# MJ808_clone_-_all_driver_-_POC.net
KiCad netlist of a schematic drawn in EAGLE
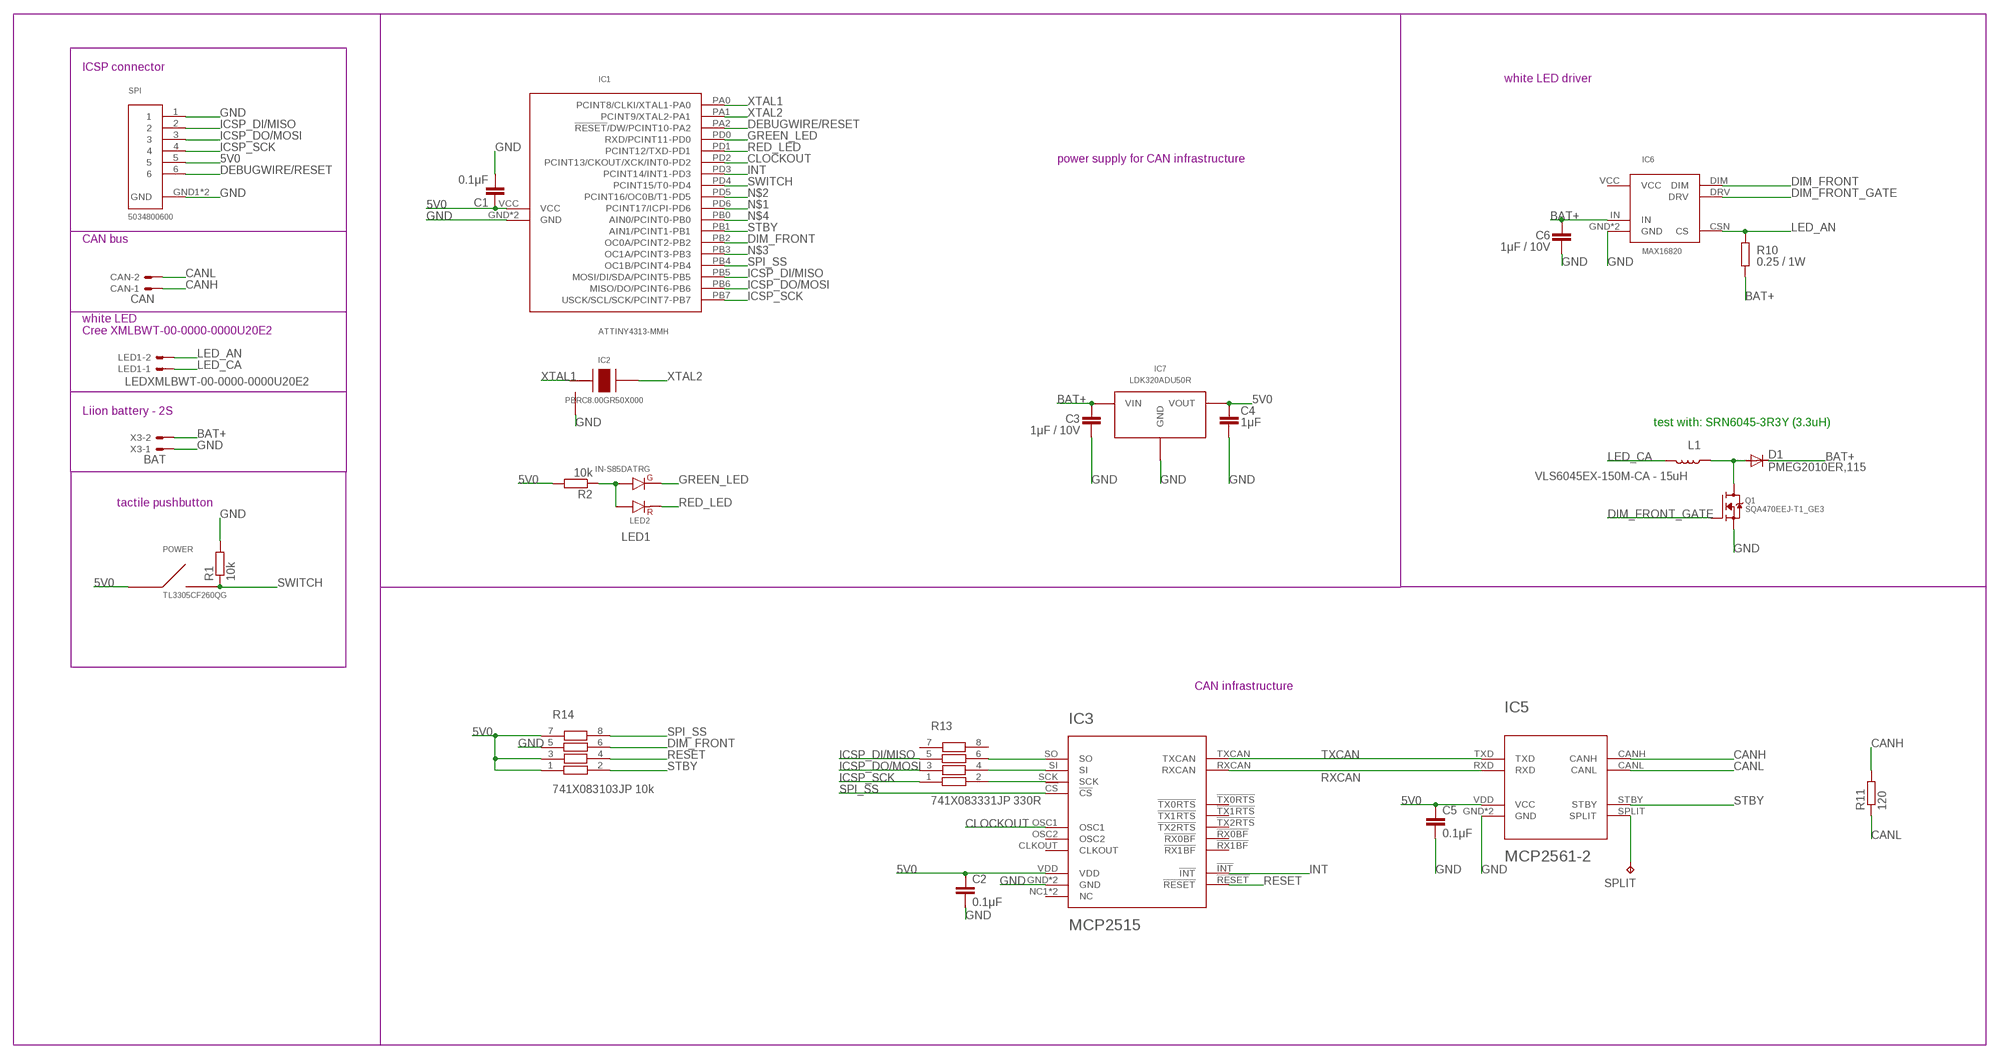
[diagram p0: schematic, sheet 1]

(export (version "E")
  (design (tool "Eeschema 10.0.6"))
  (components
    (comp (ref "C1")
      (value "0.1μF")
      (footprint "eagle-import:C0402")
      (libsource (lib "eagle-import") (part "C-EUC0402"))
    )
    (comp (ref "C2")
      (value "0.1μF")
      (footprint "eagle-import:C0402")
      (libsource (lib "eagle-import") (part "C-EUC0402"))
    )
    (comp (ref "C3")
      (value "1μF / 10V")
      (footprint "eagle-import:C0402")
      (libsource (lib "eagle-import") (part "C-EUC0402"))
    )
    (comp (ref "C4")
      (value "1μF")
      (footprint "eagle-import:C0402")
      (libsource (lib "eagle-import") (part "C-EUC0402"))
    )
    (comp (ref "C5")
      (value "0.1μF")
      (footprint "eagle-import:C0402")
      (libsource (lib "eagle-import") (part "C-EUC0402"))
    )
    (comp (ref "C6")
      (value "1μF / 10V")
      (footprint "eagle-import:C0402")
      (libsource (lib "eagle-import") (part "C-EUC0402"))
    )
    (comp (ref "CAN")
      (value "CAN")
      (footprint "eagle-import:22-23-2021")
      (fields (field (name "MF") "MOLEX") (field (name "MPN") "22-23-2021"))
      (libsource (lib "eagle-import") (part "22-23-2021"))
    )
    (comp (ref "D1")
      (value "PMEG2010ER,115")
      (footprint "eagle-import:SOD123")
      (libsource (lib "eagle-import") (part "DIODE-SOD123"))
    )
    (comp (ref "IC1")
      (value "ATTINY4313-MMH")
      (footprint "eagle-import:VQFN-20")
      (fields (field (name "SPICEPREFIX") "X"))
      (libsource (lib "eagle-import") (part "ATTINY4313VQFN-20"))
    )
    (comp (ref "IC2")
      (value "PBRC8.00GR50X000")
      (footprint "eagle-import:SMT")
      (libsource (lib "eagle-import") (part "PRQV"))
    )
    (comp (ref "IC3")
      (value "MCP2515")
      (footprint "eagle-import:QFN20")
      (libsource (lib "eagle-import") (part "MCP2515-I-ML"))
    )
    (comp (ref "IC5")
      (value "MCP2561-2")
      (footprint "eagle-import:DFN10")
      (libsource (lib "eagle-import") (part "MCP2561-2"))
    )
    (comp (ref "IC6")
      (value "MAX16820")
      (footprint "eagle-import:TDFN-6-EP")
      (libsource (lib "eagle-import") (part "MAX16820"))
    )
    (comp (ref "IC7")
      (value "LDK320ADU50R")
      (footprint "eagle-import:SOT-89")
      (libsource (lib "eagle-import") (part "LDO"))
    )
    (comp (ref "L1")
      (value "VLS6045EX-150M-CA - 15uH")
      (footprint "eagle-import:SRN6045")
      (libsource (lib "eagle-import") (part "INDUCTOR-SRN6045-33UH"))
    )
    (comp (ref "LED1")
      (value "LEDXMLBWT-00-0000-0000U20E2")
      (footprint "eagle-import:22-23-2021")
      (fields (field (name "MF") "MOLEX") (field (name "MPN") "22-23-2021"))
      (libsource (lib "eagle-import") (part "22-23-2021"))
    )
    (comp (ref "LED2")
      (value "IN-S85DATRG")
      (footprint "eagle-import:SMD")
      (libsource (lib "eagle-import") (part "APHBM2012LSURKZGKC"))
    )
    (comp (ref "POWER")
      (value "TL3305CF260QG")
      (footprint "eagle-import:SMD")
      (libsource (lib "eagle-import") (part "TL3305-844809"))
    )
    (comp (ref "Q1")
      (value "SQA470EEJ-T1_GE3")
      (footprint "eagle-import:SC-70-6")
      (libsource (lib "eagle-import") (part "SIA456DJ"))
    )
    (comp (ref "R1")
      (value "10k")
      (footprint "eagle-import:R0402")
      (libsource (lib "eagle-import") (part "R-EU_R0402"))
    )
    (comp (ref "R2")
      (value "10k")
      (footprint "eagle-import:R0402")
      (libsource (lib "eagle-import") (part "R-EU_R0402"))
    )
    (comp (ref "R10")
      (value "0.25 / 1W")
      (footprint "eagle-import:R1210")
      (libsource (lib "eagle-import") (part "R-EU_R1210"))
    )
    (comp (ref "R11")
      (value "120")
      (footprint "eagle-import:R0805")
      (libsource (lib "eagle-import") (part "R-EU_R0805"))
    )
    (comp (ref "R13")
      (value "741X083331JP 330R")
      (footprint "eagle-import:0402")
      (libsource (lib "eagle-import") (part "741X083331JP"))
    )
    (comp (ref "R14")
      (value "741X083103JP 10k")
      (footprint "eagle-import:0402")
      (libsource (lib "eagle-import") (part "741X083331JP"))
    )
    (comp (ref "SPI")
      (value "5034800600")
      (footprint "eagle-import:SMT")
      (libsource (lib "eagle-import") (part "5034800600"))
    )
    (comp (ref "SPLIT")
      (value "TPB2,54")
      (footprint "eagle-import:B2,54")
      (libsource (lib "eagle-import") (part "TPB2,54"))
    )
    (comp (ref "X3")
      (value "BAT")
      (footprint "eagle-import:22-23-2021")
      (fields (field (name "MF") "MOLEX") (field (name "MPN") "22-23-2021"))
      (libsource (lib "eagle-import") (part "22-23-2021"))
    )
  )
  (nets
    (net (code "1") (name "/5V0") (class "Default")
      (node (ref "C1") (pin "1") (pinfunction "1_1") (pintype "passive"))
      (node (ref "C2") (pin "1") (pinfunction "1_1") (pintype "passive"))
      (node (ref "C4") (pin "2") (pinfunction "2_2") (pintype "passive"))
      (node (ref "C5") (pin "1") (pinfunction "1_1") (pintype "passive"))
      (node (ref "IC1") (pin "VCC") (pinfunction "VCC_VCC") (pintype "bidirectional"))
      (node (ref "IC3") (pin "VDD") (pinfunction "VDD_VDD") (pintype "power_in"))
      (node (ref "IC5") (pin "VDD") (pinfunction "VCC_VDD") (pintype "power_in"))
      (node (ref "IC7") (pin "VOUT") (pinfunction "VOUT_VOUT") (pintype "bidirectional"))
      (node (ref "POWER") (pin "1") (pinfunction "P$1_1") (pintype "bidirectional"))
      (node (ref "POWER") (pin "2") (pinfunction "P$1_2") (pintype "bidirectional"))
      (node (ref "R14") (pin "1") (pinfunction "1_1") (pintype "bidirectional"))
      (node (ref "R14") (pin "3") (pinfunction "3_3") (pintype "bidirectional"))
      (node (ref "R14") (pin "7") (pinfunction "7_7") (pintype "bidirectional"))
      (node (ref "R2") (pin "2") (pinfunction "2_2") (pintype "passive"))
      (node (ref "SPI") (pin "5") (pinfunction "5_5") (pintype "bidirectional"))
    )
    (net (code "2") (name "/BAT+") (class "Default")
      (node (ref "C3") (pin "1") (pinfunction "1_1") (pintype "passive"))
      (node (ref "C6") (pin "1") (pinfunction "1_1") (pintype "passive"))
      (node (ref "D1") (pin "C") (pinfunction "C_C") (pintype "passive"))
      (node (ref "IC6") (pin "IN") (pinfunction "IN_IN") (pintype "power_in"))
      (node (ref "IC7") (pin "VIN") (pinfunction "VIN_VIN") (pintype "bidirectional"))
      (node (ref "R10") (pin "2") (pinfunction "2_2") (pintype "passive"))
      (node (ref "X3") (pin "2") (pinfunction "S_2") (pintype "passive"))
    )
    (net (code "3") (name "/CANH") (class "Default")
      (node (ref "CAN") (pin "1") (pinfunction "S_1") (pintype "passive"))
      (node (ref "IC5") (pin "CANH") (pinfunction "CANH_CANH") (pintype "bidirectional"))
      (node (ref "R11") (pin "2") (pinfunction "2_2") (pintype "passive"))
    )
    (net (code "4") (name "/CANL") (class "Default")
      (node (ref "CAN") (pin "2") (pinfunction "S_2") (pintype "passive"))
      (node (ref "IC5") (pin "CANL") (pinfunction "CANL_CANL") (pintype "bidirectional"))
      (node (ref "R11") (pin "1") (pinfunction "1_1") (pintype "passive"))
    )
    (net (code "5") (name "/CLOCKOUT") (class "Default")
      (node (ref "IC1") (pin "PD2") (pinfunction "PCINT13/CKOUT/XCK/INT0-PD2_PD2") (pintype "bidirectional"))
      (node (ref "IC3") (pin "OSC1") (pinfunction "OSC1_OSC1") (pintype "bidirectional"))
    )
    (net (code "6") (name "/DEBUGWIRE{slash}RESET") (class "Default")
      (node (ref "IC1") (pin "PA2") (pinfunction "~{RESET}/DW/PCINT10-PA2_PA2") (pintype "bidirectional"))
      (node (ref "SPI") (pin "6") (pinfunction "6_6") (pintype "bidirectional"))
    )
    (net (code "7") (name "/DIM_FRONT") (class "Default")
      (node (ref "IC1") (pin "PB2") (pinfunction "OC0A/PCINT2-PB2_PB2") (pintype "bidirectional"))
      (node (ref "IC6") (pin "DIM") (pinfunction "DIM_DIM") (pintype "bidirectional"))
      (node (ref "R14") (pin "6") (pinfunction "6_6") (pintype "bidirectional"))
    )
    (net (code "8") (name "/DIM_FRONT_GATE") (class "Default")
      (node (ref "IC6") (pin "DRV") (pinfunction "DRV_DRV") (pintype "bidirectional"))
      (node (ref "Q1") (pin "G") (pinfunction "G_G") (pintype "passive"))
    )
    (net (code "9") (name "/GND") (class "Default")
      (node (ref "C1") (pin "2") (pinfunction "2_2") (pintype "passive"))
      (node (ref "C2") (pin "2") (pinfunction "2_2") (pintype "passive"))
      (node (ref "C3") (pin "2") (pinfunction "2_2") (pintype "passive"))
      (node (ref "C4") (pin "1") (pinfunction "1_1") (pintype "passive"))
      (node (ref "C5") (pin "2") (pinfunction "2_2") (pintype "passive"))
      (node (ref "C6") (pin "2") (pinfunction "2_2") (pintype "passive"))
      (node (ref "IC1") (pin "GND") (pinfunction "GND_GND") (pintype "bidirectional"))
      (node (ref "IC1") (pin "GND1") (pinfunction "GND_GND1") (pintype "bidirectional"))
      (node (ref "IC2") (pin "GND") (pinfunction "GND_GND") (pintype "bidirectional"))
      (node (ref "IC3") (pin "GND") (pinfunction "GND_GND") (pintype "power_in"))
      (node (ref "IC3") (pin "GND6") (pinfunction "GND_GND6") (pintype "power_in"))
      (node (ref "IC5") (pin "GND") (pinfunction "GND_GND") (pintype "power_in"))
      (node (ref "IC5") (pin "VSS") (pinfunction "GND_VSS") (pintype "power_in"))
      (node (ref "IC6") (pin "GND") (pinfunction "GND_GND") (pintype "power_in"))
      (node (ref "IC6") (pin "GND1") (pinfunction "GND_GND1") (pintype "power_in"))
      (node (ref "IC7") (pin "GND") (pinfunction "GND_GND") (pintype "bidirectional"))
      (node (ref "Q1") (pin "S") (pinfunction "S_S") (pintype "passive"))
      (node (ref "R1") (pin "2") (pinfunction "2_2") (pintype "passive"))
      (node (ref "R14") (pin "5") (pinfunction "5_5") (pintype "bidirectional"))
      (node (ref "SPI") (pin "1") (pinfunction "1_1") (pintype "bidirectional"))
      (node (ref "SPI") (pin "GND1") (pinfunction "GND_GND1") (pintype "bidirectional"))
      (node (ref "SPI") (pin "GND2") (pinfunction "GND_GND2") (pintype "bidirectional"))
      (node (ref "X3") (pin "1") (pinfunction "S_1") (pintype "passive"))
    )
    (net (code "10") (name "/GREEN_LED") (class "Default")
      (node (ref "IC1") (pin "PD0") (pinfunction "RXD/PCINT11-PD0_PD0") (pintype "bidirectional"))
      (node (ref "LED2") (pin "3") (pinfunction "3_3") (pintype "bidirectional"))
    )
    (net (code "11") (name "/ICSP_DI{slash}MISO") (class "Default")
      (node (ref "IC1") (pin "PB5") (pinfunction "MOSI/DI/SDA/PCINT5-PB5_PB5") (pintype "bidirectional"))
      (node (ref "R13") (pin "5") (pinfunction "5_5") (pintype "bidirectional"))
      (node (ref "SPI") (pin "2") (pinfunction "2_2") (pintype "bidirectional"))
    )
    (net (code "12") (name "/ICSP_DO{slash}MOSI") (class "Default")
      (node (ref "IC1") (pin "PB6") (pinfunction "MISO/DO/PCINT6-PB6_PB6") (pintype "bidirectional"))
      (node (ref "R13") (pin "3") (pinfunction "3_3") (pintype "bidirectional"))
      (node (ref "SPI") (pin "3") (pinfunction "3_3") (pintype "bidirectional"))
    )
    (net (code "13") (name "/ICSP_SCK") (class "Default")
      (node (ref "IC1") (pin "PB7") (pinfunction "USCK/SCL/SCK/PCINT7-PB7_PB7") (pintype "bidirectional"))
      (node (ref "R13") (pin "1") (pinfunction "1_1") (pintype "bidirectional"))
      (node (ref "SPI") (pin "4") (pinfunction "4_4") (pintype "bidirectional"))
    )
    (net (code "14") (name "/INT") (class "Default")
      (node (ref "IC1") (pin "PD3") (pinfunction "PCINT14/INT1-PD3_PD3") (pintype "bidirectional"))
      (node (ref "IC3") (pin "!INT!") (pinfunction "~{INT}_!INT!") (pintype "bidirectional"))
    )
    (net (code "15") (name "/LED1") (class "Default")
      (node (ref "LED2") (pin "1") (pinfunction "1_1") (pintype "bidirectional"))
      (node (ref "LED2") (pin "4") (pinfunction "4_4") (pintype "bidirectional"))
      (node (ref "R2") (pin "1") (pinfunction "1_1") (pintype "passive"))
    )
    (net (code "16") (name "/LED_AN") (class "Default")
      (node (ref "IC6") (pin "CSN") (pinfunction "CS_CSN") (pintype "bidirectional"))
      (node (ref "LED1") (pin "2") (pinfunction "S_2") (pintype "passive"))
      (node (ref "R10") (pin "1") (pinfunction "1_1") (pintype "passive"))
    )
    (net (code "17") (name "/LED_CA") (class "Default")
      (node (ref "L1") (pin "2") (pinfunction "2_2") (pintype "passive"))
      (node (ref "LED1") (pin "1") (pinfunction "S_1") (pintype "passive"))
    )
    (net (code "18") (name "/N$1") (class "Default")
      (node (ref "IC1") (pin "PD6") (pinfunction "PCINT17/ICPI-PD6_PD6") (pintype "bidirectional"))
    )
    (net (code "19") (name "/N$2") (class "Default")
      (node (ref "IC1") (pin "PD5") (pinfunction "PCINT16/OC0B/T1-PD5_PD5") (pintype "bidirectional"))
    )
    (net (code "20") (name "/N$3") (class "Default")
      (node (ref "IC1") (pin "PB3") (pinfunction "OC1A/PCINT3-PB3_PB3") (pintype "bidirectional"))
    )
    (net (code "21") (name "/N$4") (class "Default")
      (node (ref "IC1") (pin "PB0") (pinfunction "AIN0/PCINT0-PB0_PB0") (pintype "bidirectional"))
    )
    (net (code "22") (name "/RED_LED") (class "Default")
      (node (ref "IC1") (pin "PD1") (pinfunction "PCINT12/TXD-PD1_PD1") (pintype "bidirectional"))
      (node (ref "LED2") (pin "2") (pinfunction "2_2") (pintype "bidirectional"))
    )
    (net (code "23") (name "/RESET") (class "Default")
      (node (ref "IC3") (pin "!RESET!") (pinfunction "~{RESET}_!RESET!") (pintype "bidirectional"))
      (node (ref "R14") (pin "4") (pinfunction "4_4") (pintype "bidirectional"))
    )
    (net (code "24") (name "/RXCAN") (class "Default")
      (node (ref "IC3") (pin "RXCAN") (pinfunction "RXCAN_RXCAN") (pintype "input"))
      (node (ref "IC5") (pin "RXD") (pinfunction "RXD_RXD") (pintype "output"))
    )
    (net (code "25") (name "/SPI_SS") (class "Default")
      (node (ref "IC1") (pin "PB4") (pinfunction "OC1B/PCINT4-PB4_PB4") (pintype "bidirectional"))
      (node (ref "IC3") (pin "!CS!") (pinfunction "~{CS}_!CS!") (pintype "bidirectional"))
      (node (ref "R14") (pin "8") (pinfunction "8_8") (pintype "bidirectional"))
    )
    (net (code "26") (name "/STBY") (class "Default")
      (node (ref "IC1") (pin "PB1") (pinfunction "AIN1/PCINT1-PB1_PB1") (pintype "bidirectional"))
      (node (ref "IC5") (pin "STBY") (pinfunction "STBY_STBY") (pintype "bidirectional"))
      (node (ref "R14") (pin "2") (pinfunction "2_2") (pintype "bidirectional"))
    )
    (net (code "27") (name "/SWITCH") (class "Default")
      (node (ref "IC1") (pin "PD4") (pinfunction "PCINT15/T0-PD4_PD4") (pintype "bidirectional"))
      (node (ref "POWER") (pin "3") (pinfunction "P$2_3") (pintype "bidirectional"))
      (node (ref "POWER") (pin "4") (pinfunction "P$2_4") (pintype "bidirectional"))
      (node (ref "R1") (pin "1") (pinfunction "1_1") (pintype "passive"))
    )
    (net (code "28") (name "/TXCAN") (class "Default")
      (node (ref "IC3") (pin "TXCAN") (pinfunction "TXCAN_TXCAN") (pintype "output"))
      (node (ref "IC5") (pin "TXD") (pinfunction "TXD_TXD") (pintype "input"))
    )
    (net (code "29") (name "/VCC") (class "Default")
      (node (ref "IC6") (pin "VCC") (pinfunction "VCC_VCC") (pintype "power_in"))
    )
    (net (code "30") (name "/XTAL1") (class "Default")
      (node (ref "IC1") (pin "PA0") (pinfunction "PCINT8/CLKI/XTAL1-PA0_PA0") (pintype "bidirectional"))
      (node (ref "IC2") (pin "XTAL1") (pinfunction "XTAL1_XTAL1") (pintype "bidirectional"))
    )
    (net (code "31") (name "/XTAL2") (class "Default")
      (node (ref "IC1") (pin "PA1") (pinfunction "PCINT9/XTAL2-PA1_PA1") (pintype "bidirectional"))
      (node (ref "IC2") (pin "XTAL2") (pinfunction "XTAL2_XTAL2") (pintype "bidirectional"))
    )
    (net (code "32") (name "Net-(D1-PadA)") (class "Default")
      (node (ref "D1") (pin "A") (pinfunction "A_A") (pintype "passive"))
      (node (ref "L1") (pin "1") (pinfunction "1_1") (pintype "passive"))
      (node (ref "Q1") (pin "D") (pinfunction "D_D") (pintype "passive"))
    )
    (net (code "33") (name "Net-(IC3-PadSCK)") (class "Default")
      (node (ref "IC3") (pin "SCK") (pinfunction "SCK_SCK") (pintype "bidirectional"))
      (node (ref "R13") (pin "2") (pinfunction "2_2") (pintype "bidirectional"))
    )
    (net (code "34") (name "Net-(IC3-PadSI)") (class "Default")
      (node (ref "IC3") (pin "SI") (pinfunction "SI_SI") (pintype "input"))
      (node (ref "R13") (pin "4") (pinfunction "4_4") (pintype "bidirectional"))
    )
    (net (code "35") (name "Net-(IC3-PadSO)") (class "Default")
      (node (ref "IC3") (pin "SO") (pinfunction "SO_SO") (pintype "output"))
      (node (ref "R13") (pin "6") (pinfunction "6_6") (pintype "bidirectional"))
    )
    (net (code "36") (name "Net-(IC5-PadSPLIT)") (class "Default")
      (node (ref "IC5") (pin "SPLIT") (pinfunction "SPLIT_SPLIT") (pintype "bidirectional"))
      (node (ref "SPLIT") (pin "TP") (pinfunction "TP_TP") (pintype "input"))
    )
    (net (code "37") (name "unconnected-(IC3-NC-PadNC1)") (class "Default")
      (node (ref "IC3") (pin "NC1") (pinfunction "NC_NC1") (pintype "no_connect"))
    )
    (net (code "38") (name "unconnected-(IC3-NC-PadNC2)") (class "Default")
      (node (ref "IC3") (pin "NC2") (pinfunction "NC_NC2") (pintype "no_connect"))
    )
    (net (code "39") (name "unconnected-(IC3-PadCLKOUT)") (class "Default")
      (node (ref "IC3") (pin "CLKOUT") (pinfunction "CLKOUT_CLKOUT") (pintype "bidirectional"))
    )
    (net (code "40") (name "unconnected-(IC3-PadOSC2)") (class "Default")
      (node (ref "IC3") (pin "OSC2") (pinfunction "OSC2_OSC2") (pintype "bidirectional"))
    )
    (net (code "41") (name "unconnected-(IC3-~{RX0BF}-Pad!RX0BF!)") (class "Default")
      (node (ref "IC3") (pin "!RX0BF!") (pinfunction "~{RX0BF}_!RX0BF!") (pintype "bidirectional"))
    )
    (net (code "42") (name "unconnected-(IC3-~{RX1BF}-Pad!RX1BF!)") (class "Default")
      (node (ref "IC3") (pin "!RX1BF!") (pinfunction "~{RX1BF}_!RX1BF!") (pintype "bidirectional"))
    )
    (net (code "43") (name "unconnected-(IC3-~{TX0RTS}-Pad!TX0RTS!)") (class "Default")
      (node (ref "IC3") (pin "!TX0RTS!") (pinfunction "~{TX0RTS}_!TX0RTS!") (pintype "bidirectional"))
    )
    (net (code "44") (name "unconnected-(IC3-~{TX1RTS}-Pad!TX1RTS!)") (class "Default")
      (node (ref "IC3") (pin "!TX1RTS!") (pinfunction "~{TX1RTS}_!TX1RTS!") (pintype "bidirectional"))
    )
    (net (code "45") (name "unconnected-(IC3-~{TX2RTS}-Pad!TX2RTS!)") (class "Default")
      (node (ref "IC3") (pin "!TX2RTS!") (pinfunction "~{TX2RTS}_!TX2RTS!") (pintype "bidirectional"))
    )
    (net (code "46") (name "unconnected-(R13-Pad7)") (class "Default")
      (node (ref "R13") (pin "7") (pinfunction "7_7") (pintype "bidirectional"))
    )
    (net (code "47") (name "unconnected-(R13-Pad8)") (class "Default")
      (node (ref "R13") (pin "8") (pinfunction "8_8") (pintype "bidirectional"))
    )
  )
)
